# NDIR_SensorInterface.net
KiCad netlist of a schematic drawn in EAGLE
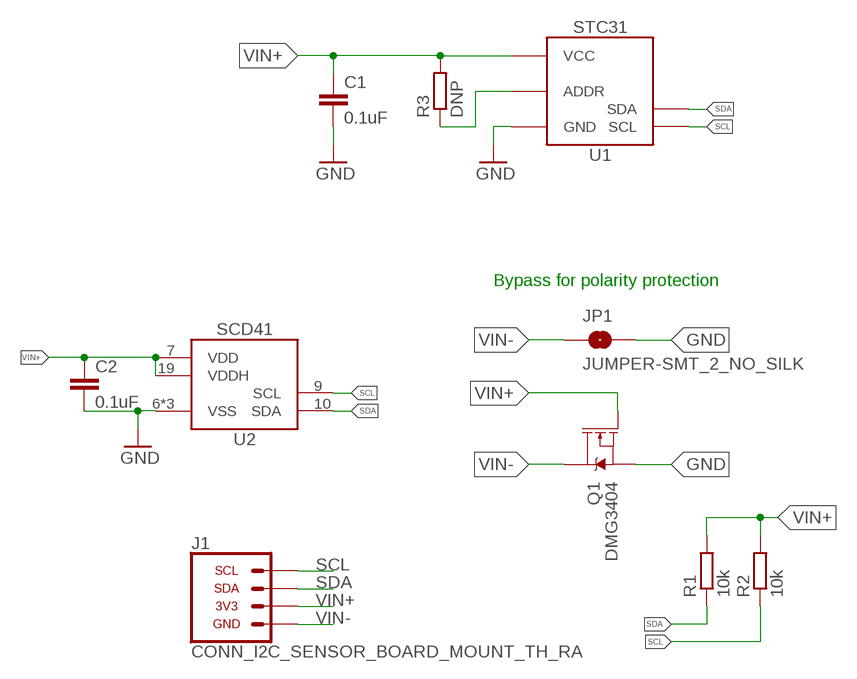
[diagram p0: schematic, sheet 1]

(export (version "E")
  (design (tool "Eeschema 10.0.6"))
  (components
    (comp (ref "C1")
      (value "0.1uF")
      (footprint "eagle-import:C0603")
      (fields (field (name "MF") "Murata") (field (name "MPN") "GCM188R71E104KA57D"))
      (libsource (lib "eagle-import") (part "C-EUC06030.1UF"))
    )
    (comp (ref "C2")
      (value "0.1uF")
      (footprint "eagle-import:C0603")
      (fields (field (name "MF") "Murata") (field (name "MPN") "GCM188R71E104KA57D"))
      (libsource (lib "eagle-import") (part "C-EUC06030.1UF"))
    )
    (comp (ref "J1")
      (value "CONN_I2C_SENSOR_BOARD_MOUNT_TH_RA")
      (footprint "eagle-import:CONEC_43-01204")
      (fields (field (name "MF") "Conec") (field (name "MPN") "43-01204"))
      (libsource (lib "eagle-import") (part "CONN_I2C_SENSOR_BOARD_MOUNT_TH_RA"))
    )
    (comp (ref "JP1")
      (value "JUMPER-SMT_2_NO_SILK")
      (footprint "eagle-import:SMT-JUMPER_2_NO_SILK")
      (libsource (lib "eagle-import") (part "JUMPER-SMT_2_NO_SILK"))
    )
    (comp (ref "Q1")
      (value "DMG3404")
      (footprint "eagle-import:SOT23-3")
      (fields (field (name "MF") "Diodes Incorporated") (field (name "MPN") "DMG3404L-7"))
      (libsource (lib "eagle-import") (part "MOSFET-NCH-DMG3404L"))
    )
    (comp (ref "R1")
      (value "10k")
      (footprint "eagle-import:R0603")
      (fields (field (name "MF") "Yageo") (field (name "MPN") "RC0603FR-0710KL"))
      (libsource (lib "eagle-import") (part "R-EU_R060310K"))
    )
    (comp (ref "R2")
      (value "10k")
      (footprint "eagle-import:R0603")
      (fields (field (name "MF") "Yageo") (field (name "MPN") "RC0603FR-0710KL"))
      (libsource (lib "eagle-import") (part "R-EU_R060310K"))
    )
    (comp (ref "R3")
      (value "DNP")
      (footprint "eagle-import:R0603")
      (fields (field (name "MF") "Yageo"))
      (libsource (lib "eagle-import") (part "R-EU_R0603"))
    )
    (comp (ref "U1")
      (value "STC31")
      (footprint "eagle-import:STC31")
      (fields (field (name "DISP") "STC31") (field (name "MF") "Sensirion") (field (name "MPN") "STC31-C-R3"))
      (libsource (lib "eagle-import") (part "STC31"))
    )
    (comp (ref "U2")
      (value "SCD41")
      (footprint "eagle-import:SCD4X")
      (fields (field (name "DISP") "SCD41") (field (name "MF") "Sensirion") (field (name "MPN") "SCD41-D-R2"))
      (libsource (lib "eagle-import") (part "SCD41"))
    )
  )
  (nets
    (net (code "1") (name "GND") (class "Default")
      (node (ref "C1") (pin "2") (pinfunction "2_2") (pintype "passive"))
      (node (ref "C2") (pin "2") (pinfunction "2_2") (pintype "passive"))
      (node (ref "JP1") (pin "2") (pinfunction "2_2") (pintype "passive"))
      (node (ref "Q1") (pin "2") (pinfunction "S_2") (pintype "bidirectional"))
      (node (ref "U1") (pin "1") (pinfunction "GND_1") (pintype "power_in"))
      (node (ref "U1") (pin "11") (pinfunction "GND_11") (pintype "power_in"))
      (node (ref "U1") (pin "5") (pinfunction "GND_5") (pintype "power_in"))
      (node (ref "U1") (pin "9") (pinfunction "GND_9") (pintype "power_in"))
      (node (ref "U1") (pin "EP") (pinfunction "GND_EP") (pintype "power_in"))
      (node (ref "U2") (pin "20") (pinfunction "VSS_20") (pintype "power_in"))
      (node (ref "U2") (pin "6") (pinfunction "VSS_6") (pintype "power_in"))
      (node (ref "U2") (pin "EP") (pinfunction "VSS_EP") (pintype "power_in"))
    )
    (net (code "2") (name "Net-(U1-ADDR)") (class "Default")
      (node (ref "R3") (pin "1") (pinfunction "1_1") (pintype "passive"))
      (node (ref "U1") (pin "3") (pinfunction "ADDR_3") (pintype "input"))
    )
    (net (code "3") (name "SCL") (class "Default")
      (node (ref "J1") (pin "3") (pinfunction "SCL_3") (pintype "passive"))
      (node (ref "R2") (pin "1") (pinfunction "1_1") (pintype "passive"))
      (node (ref "U1") (pin "4") (pinfunction "SCL_4") (pintype "input"))
      (node (ref "U2") (pin "9") (pinfunction "SCL_9") (pintype "input"))
    )
    (net (code "4") (name "SDA") (class "Default")
      (node (ref "J1") (pin "1") (pinfunction "SDA_1") (pintype "passive"))
      (node (ref "R1") (pin "1") (pinfunction "1_1") (pintype "passive"))
      (node (ref "U1") (pin "7") (pinfunction "SDA_7") (pintype "bidirectional"))
      (node (ref "U2") (pin "10") (pinfunction "SDA_10") (pintype "bidirectional"))
    )
    (net (code "5") (name "VIN+") (class "Default")
      (node (ref "C1") (pin "1") (pinfunction "1_1") (pintype "passive"))
      (node (ref "C2") (pin "1") (pinfunction "1_1") (pintype "passive"))
      (node (ref "J1") (pin "2") (pinfunction "3V3_2") (pintype "passive"))
      (node (ref "Q1") (pin "1") (pinfunction "G_1") (pintype "bidirectional"))
      (node (ref "R1") (pin "2") (pinfunction "2_2") (pintype "passive"))
      (node (ref "R2") (pin "2") (pinfunction "2_2") (pintype "passive"))
      (node (ref "R3") (pin "2") (pinfunction "2_2") (pintype "passive"))
      (node (ref "U1") (pin "6") (pinfunction "VCC_6") (pintype "power_in"))
      (node (ref "U2") (pin "19") (pinfunction "VDDH_19") (pintype "power_in"))
      (node (ref "U2") (pin "7") (pinfunction "VDD_7") (pintype "power_in"))
    )
    (net (code "6") (name "VIN-") (class "Default")
      (node (ref "J1") (pin "4") (pinfunction "GND_4") (pintype "passive"))
      (node (ref "JP1") (pin "1") (pinfunction "1_1") (pintype "passive"))
      (node (ref "Q1") (pin "3") (pinfunction "D_3") (pintype "bidirectional"))
    )
  )
)
